# Supply.net
KiCad netlist of a schematic drawn in Altium Designer
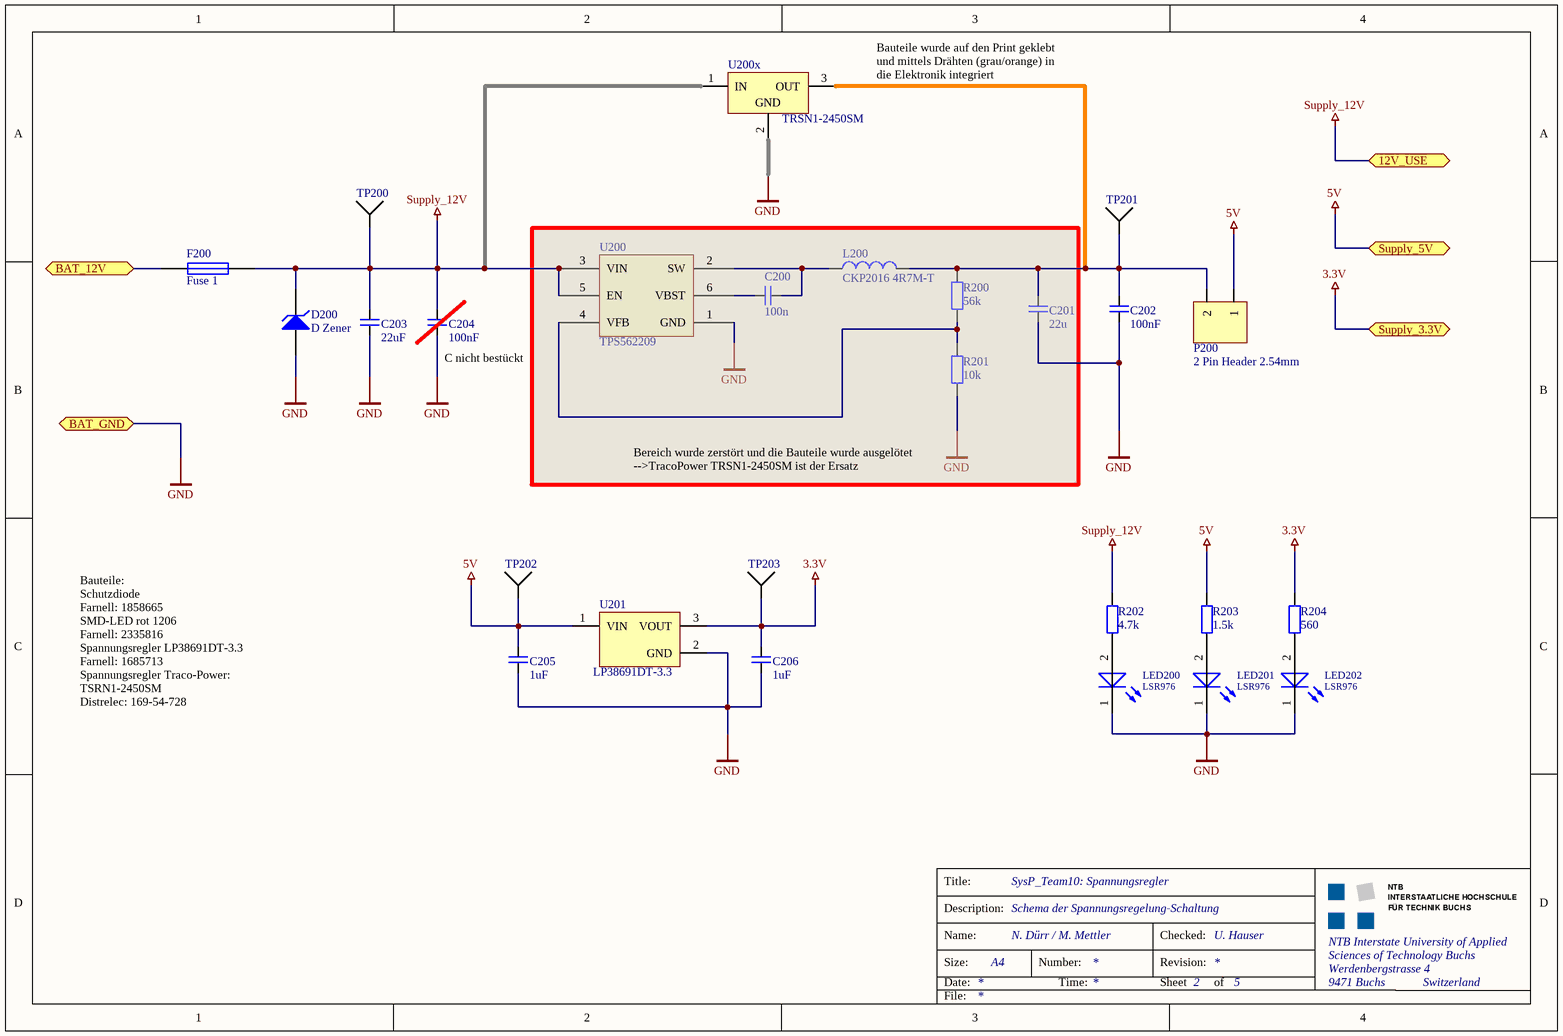
[diagram p0: Supply.SchDoc]

(export (version "E")
  (design (tool "Eeschema 10.0.6"))
  (components
    (comp (ref "C200")
      (value "100n")
      (footprint "CAPC0805")
      (description "X7R MLCC 0805 (2012 Metric)")
      (fields (field (name "TOLERANCE") "10%"))
      (libsource (lib "Motortreiber") (part "C Bipolar 0805"))
    )
    (comp (ref "C201")
      (value "22u")
      (footprint "C0805")
      (description "X7R MLCC 1206 (3016 Metric)")
      (fields (field (name "TOLERANCE") "10%"))
      (libsource (lib "Motortreiber") (part "C Bipolar 1206"))
    )
    (comp (ref "C202")
      (value "100nF")
      (footprint "C0805")
      (description "X7R MLCC 1206 (3016 Metric)")
      (fields (field (name "TOLERANCE") "10%"))
      (libsource (lib "Motortreiber") (part "C Bipolar 1206"))
    )
    (comp (ref "C203")
      (value "22uF")
      (footprint "CAPC0805")
      (description "X7R MLCC 0805 (2012 Metric)")
      (fields (field (name "TOLERANCE") "10%"))
      (libsource (lib "Motortreiber") (part "C Bipolar 0805"))
    )
    (comp (ref "C204")
      (value "100nF")
      (footprint "CAPC0805")
      (description "X7R MLCC 0805 (2012 Metric)")
      (fields (field (name "TOLERANCE") "10%"))
      (libsource (lib "Motortreiber") (part "C Bipolar 0805"))
    )
    (comp (ref "C205")
      (value "1uF")
      (footprint "CAPC0805")
      (description "X7R MLCC 0805 (2012 Metric)")
      (fields (field (name "TOLERANCE") "10%"))
      (libsource (lib "Motortreiber") (part "C Bipolar 0805"))
    )
    (comp (ref "C206")
      (value "1uF")
      (footprint "CAPC0805")
      (description "X7R MLCC 0805 (2012 Metric)")
      (fields (field (name "TOLERANCE") "10%"))
      (libsource (lib "Motortreiber") (part "C Bipolar 0805"))
    )
    (comp (ref "D200")
      (value "D Zener")
      (footprint "SMD_2Pin")
      (description "Zener Diode")
      (fields (field (name "PUBLISHER") "Altium Limited"))
      (libsource (lib "Miscellaneous Devices") (part "D Zener"))
    )
    (comp (ref "F200")
      (value "Fuse 1")
      (footprint "Connector_2")
      (description "Fuse")
      (fields (field (name "PUBLISHER") "Altium Limited"))
      (libsource (lib "Miscellaneous Devices") (part "Fuse 1"))
    )
    (comp (ref "L200")
      (value "CKP2016 4R7M-T")
      (footprint "IND0806")
      (description "MULTILAYER CHIP POWER INDUCTORS")
      (libsource (lib "altium-import") (part "root_0_L_"))
    )
    (comp (ref "LED200")
      (value "LSR976")
      (footprint "CAPC1206")
      (description "Hyper ChipLED, Red,")
      (fields (field (name "MANUFACTURER") "OSRAM") (field (name "PUBLISHER") "Stefan Ursella, M.Eng"))
      (libsource (lib "SysP2015") (part "OSR_LSR976_0805(1K2A)"))
    )
    (comp (ref "LED201")
      (value "LSR976")
      (footprint "CAPC1206")
      (description "Hyper ChipLED, Red,")
      (fields (field (name "MANUFACTURER") "OSRAM") (field (name "PUBLISHER") "Stefan Ursella, M.Eng"))
      (libsource (lib "SysP2015") (part "OSR_LSR976_0805(1K2A)"))
    )
    (comp (ref "LED202")
      (value "LSR976")
      (footprint "CAPC1206")
      (description "Hyper ChipLED, Red,")
      (fields (field (name "MANUFACTURER") "OSRAM") (field (name "PUBLISHER") "Stefan Ursella, M.Eng"))
      (libsource (lib "SysP2015") (part "OSR_LSR976_0805(1K2A)"))
    )
    (comp (ref "P200")
      (value "2 Pin Header 2.54mm")
      (footprint "2Pin Header 2.54mm")
      (libsource (lib "altium-import") (part "root_3_2 Pin Connector_"))
    )
    (comp (ref "R200")
      (value "56k")
      (footprint "GEN_R0805_H")
      (description "generic resistor")
      (fields
        (field (name "MANUFACTURER") "Tbd")
        (field (name "Comment") "Generic")
        (field (name "PUBLISHER") "Altium Limited")
      )
      (libsource (lib "Motortreiber") (part "GEN_R_2"))
    )
    (comp (ref "R201")
      (value "10k")
      (footprint "GEN_R0805_H")
      (description "generic resistor")
      (fields
        (field (name "MANUFACTURER") "Tbd")
        (field (name "Comment") "Generic")
        (field (name "PUBLISHER") "Altium Limited")
      )
      (libsource (lib "Motortreiber") (part "GEN_R_2"))
    )
    (comp (ref "R202")
      (value "4.7k")
      (footprint "GEN_R0805_H")
      (description "generic resistor")
      (fields
        (field (name "MANUFACTURER") "Tbd")
        (field (name "Comment") "Generic")
        (field (name "PUBLISHER") "Altium Limited")
      )
      (libsource (lib "Motortreiber") (part "GEN_R_2"))
    )
    (comp (ref "R203")
      (value "1.5k")
      (footprint "GEN_R0805_H")
      (description "generic resistor")
      (fields
        (field (name "MANUFACTURER") "Tbd")
        (field (name "Comment") "Generic")
        (field (name "PUBLISHER") "Altium Limited")
      )
      (libsource (lib "Motortreiber") (part "GEN_R_2"))
    )
    (comp (ref "R204")
      (value "560")
      (footprint "GEN_R0805_H")
      (description "generic resistor")
      (fields
        (field (name "MANUFACTURER") "Tbd")
        (field (name "Comment") "Generic")
        (field (name "PUBLISHER") "Altium Limited")
      )
      (libsource (lib "Motortreiber") (part "GEN_R_2"))
    )
    (comp (ref "TP200")
      (value "Testpunkt 1mm")
      (footprint "GEN_TP-THT-1.1mm_1_H")
      (fields (field (name "MANUFACTURER") "Keystone Electronics") (field (name "PUBLISHER") "B.Sc. Ursella"))
      (libsource (lib "IR-Sensor") (part "Testpunkt 1mm"))
    )
    (comp (ref "TP201")
      (value "Testpunkt 1mm")
      (footprint "GEN_TP-THT-1.1mm_1_H")
      (fields (field (name "MANUFACTURER") "Keystone Electronics") (field (name "PUBLISHER") "B.Sc. Ursella"))
      (libsource (lib "IR-Sensor") (part "Testpunkt 1mm"))
    )
    (comp (ref "TP202")
      (value "Testpunkt 1mm")
      (footprint "GEN_TP-THT-1.1mm_1_H")
      (fields (field (name "MANUFACTURER") "Keystone Electronics") (field (name "PUBLISHER") "B.Sc. Ursella"))
      (libsource (lib "IR-Sensor") (part "Testpunkt 1mm"))
    )
    (comp (ref "TP203")
      (value "Testpunkt 1mm")
      (footprint "GEN_TP-THT-1.1mm_1_H")
      (fields (field (name "MANUFACTURER") "Keystone Electronics") (field (name "PUBLISHER") "B.Sc. Ursella"))
      (libsource (lib "IR-Sensor") (part "Testpunkt 1mm"))
    )
    (comp (ref "U200")
      (value "TPS562209")
      (footprint "SOT23-6")
      (description "3-A Synchronous Step-Down Voltage Regulator")
      (libsource (lib "altium-import") (part "root_0_TPS562209_"))
    )
    (comp (ref "U200x")
      (value "TRSN1-2450SM")
      (footprint "KC03")
      (description "3-Terminal Positive Regulator")
      (fields (field (name "PUBLISHER") "Altium Limited"))
      (libsource (lib "TI Power Mgt Voltage Regulator") (part "LM330KC"))
    )
    (comp (ref "U201")
      (value "LP38691DT-3.3")
      (footprint "TO_252_3")
      (description "Low Quiescent Current LDO, 3-Pin SOT-89, Extended Temperature, Tape and Reel")
      (fields (field (name "PUBLISHER") "Altium Limited"))
      (libsource (lib "Microchip Power Mgt Line Regulator") (part "MCP1700T-2302E/MB"))
    )
  )
  (nets
    (net (code "1") (name "/BAT_12V") (class "Default")
      (node (ref "F200") (pin "1") (pinfunction "1_1") (pintype "passive"))
    )
    (net (code "2") (name "3.3V") (class "Default")
      (node (ref "C206") (pin "1") (pinfunction "1_1") (pintype "passive"))
      (node (ref "R204") (pin "2") (pinfunction "2_2") (pintype "passive"))
      (node (ref "TP203") (pin "1") (pinfunction "0_1") (pintype "passive"))
      (node (ref "U201") (pin "3") (pinfunction "VOUT_3") (pintype "power_in"))
    )
    (net (code "3") (name "5V") (class "Default")
      (node (ref "C205") (pin "1") (pinfunction "1_1") (pintype "passive"))
      (node (ref "P200") (pin "1") (pinfunction "1_1") (pintype "passive"))
      (node (ref "R203") (pin "2") (pinfunction "2_2") (pintype "passive"))
      (node (ref "TP202") (pin "1") (pinfunction "0_1") (pintype "passive"))
      (node (ref "U201") (pin "1") (pinfunction "VIN_1") (pintype "power_in"))
    )
    (net (code "4") (name "GND") (class "Default")
      (node (ref "C201") (pin "2") (pinfunction "2_2") (pintype "passive"))
      (node (ref "C202") (pin "2") (pinfunction "2_2") (pintype "passive"))
      (node (ref "C203") (pin "2") (pinfunction "2_2") (pintype "passive"))
      (node (ref "C204") (pin "2") (pinfunction "2_2") (pintype "passive"))
      (node (ref "C205") (pin "2") (pinfunction "2_2") (pintype "passive"))
      (node (ref "C206") (pin "2") (pinfunction "2_2") (pintype "passive"))
      (node (ref "D200") (pin "1") (pinfunction "A_1") (pintype "passive"))
      (node (ref "LED200") (pin "1") (pinfunction "K_1") (pintype "passive"))
      (node (ref "LED201") (pin "1") (pinfunction "K_1") (pintype "passive"))
      (node (ref "LED202") (pin "1") (pinfunction "K_1") (pintype "passive"))
      (node (ref "R201") (pin "1") (pinfunction "1_1") (pintype "passive"))
      (node (ref "U200") (pin "1") (pinfunction "GND_1") (pintype "passive"))
      (node (ref "U200x") (pin "2") (pinfunction "GND_2") (pintype "power_in"))
      (node (ref "U201") (pin "2") (pinfunction "GND_2") (pintype "power_in"))
    )
    (net (code "5") (name "Net-(LED200-A)") (class "Default")
      (node (ref "LED200") (pin "2") (pinfunction "A_2") (pintype "passive"))
      (node (ref "R202") (pin "1") (pinfunction "1_1") (pintype "passive"))
    )
    (net (code "6") (name "Net-(LED201-A)") (class "Default")
      (node (ref "LED201") (pin "2") (pinfunction "A_2") (pintype "passive"))
      (node (ref "R203") (pin "1") (pinfunction "1_1") (pintype "passive"))
    )
    (net (code "7") (name "Net-(LED202-A)") (class "Default")
      (node (ref "LED202") (pin "2") (pinfunction "A_2") (pintype "passive"))
      (node (ref "R204") (pin "1") (pinfunction "1_1") (pintype "passive"))
    )
    (net (code "8") (name "Net-(TP201-0)") (class "Default")
      (node (ref "C201") (pin "1") (pinfunction "1_1") (pintype "passive"))
      (node (ref "C202") (pin "1") (pinfunction "1_1") (pintype "passive"))
      (node (ref "L200") (pin "2") (pinfunction "2_2") (pintype "passive"))
      (node (ref "P200") (pin "2") (pinfunction "2_2") (pintype "passive"))
      (node (ref "R200") (pin "2") (pinfunction "2_2") (pintype "passive"))
      (node (ref "TP201") (pin "1") (pinfunction "0_1") (pintype "passive"))
      (node (ref "U200x") (pin "3") (pinfunction "OUT_3") (pintype "power_in"))
    )
    (net (code "9") (name "Net-(U200-SW)") (class "Default")
      (node (ref "C200") (pin "2") (pinfunction "2_2") (pintype "passive"))
      (node (ref "L200") (pin "1") (pinfunction "1_1") (pintype "passive"))
      (node (ref "U200") (pin "2") (pinfunction "SW_2") (pintype "passive"))
    )
    (net (code "10") (name "Net-(U200-VBST)") (class "Default")
      (node (ref "C200") (pin "1") (pinfunction "1_1") (pintype "passive"))
      (node (ref "U200") (pin "6") (pinfunction "VBST_6") (pintype "passive"))
    )
    (net (code "11") (name "Net-(U200-VFB)") (class "Default")
      (node (ref "R200") (pin "1") (pinfunction "1_1") (pintype "passive"))
      (node (ref "R201") (pin "2") (pinfunction "2_2") (pintype "passive"))
      (node (ref "U200") (pin "4") (pinfunction "VFB_4") (pintype "passive"))
    )
    (net (code "12") (name "Supply_12V") (class "Default")
      (node (ref "C203") (pin "1") (pinfunction "1_1") (pintype "passive"))
      (node (ref "C204") (pin "1") (pinfunction "1_1") (pintype "passive"))
      (node (ref "D200") (pin "2") (pinfunction "K_2") (pintype "passive"))
      (node (ref "F200") (pin "2") (pinfunction "2_2") (pintype "passive"))
      (node (ref "R202") (pin "2") (pinfunction "2_2") (pintype "passive"))
      (node (ref "TP200") (pin "1") (pinfunction "0_1") (pintype "passive"))
      (node (ref "U200") (pin "3") (pinfunction "VIN_3") (pintype "passive"))
      (node (ref "U200") (pin "5") (pinfunction "EN_5") (pintype "passive"))
      (node (ref "U200x") (pin "1") (pinfunction "IN_1") (pintype "power_in"))
    )
  )
)
